# leds.net
KiCad netlist of a schematic drawn in EAGLE
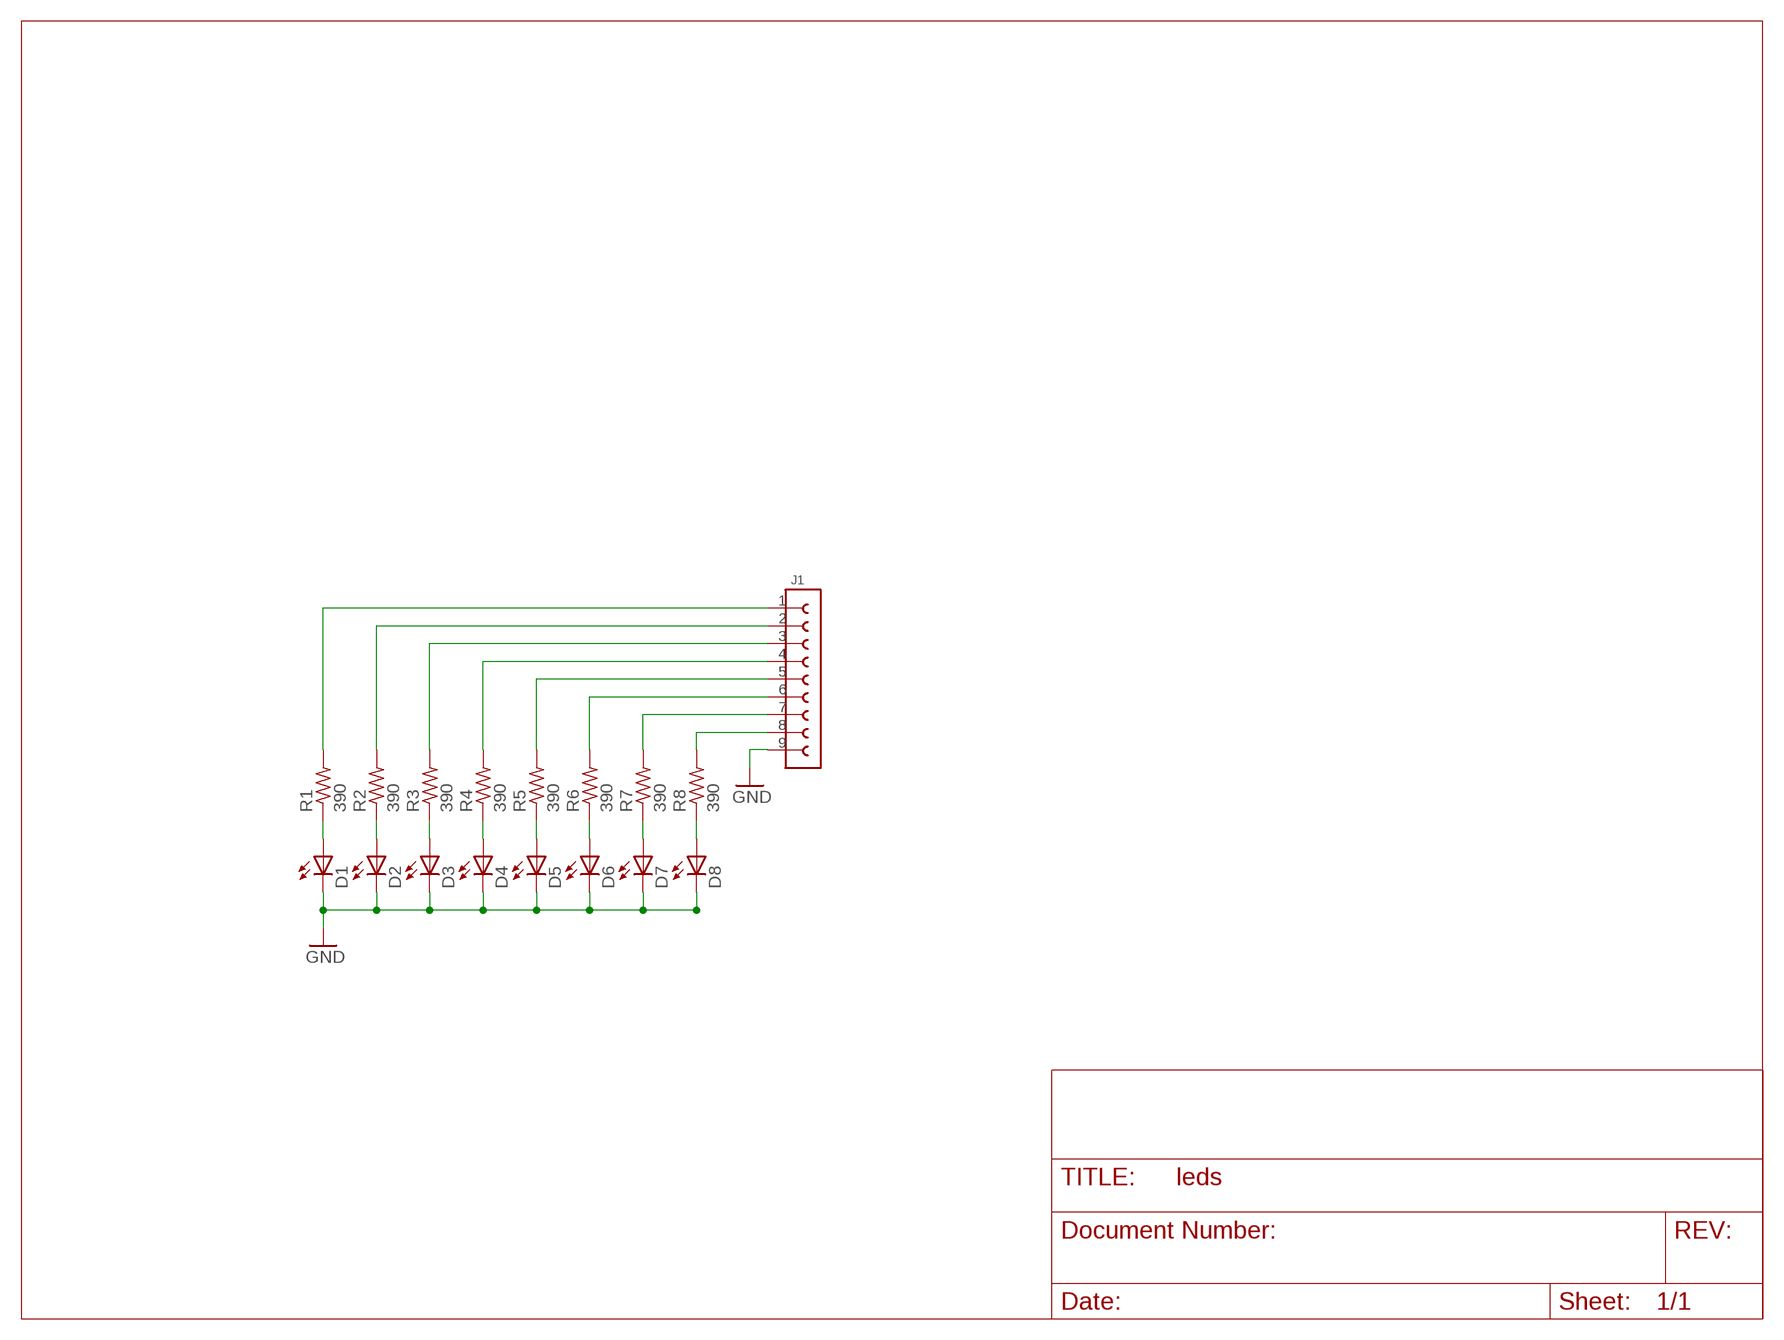
[diagram p0: schematic, sheet 1]

(export (version "E")
  (design (tool "Eeschema 10.0.6"))
  (components
    (comp (ref "D1")
      (value "SM0805AC")
      (footprint "eagle-import:D0805")
      (libsource (lib "eagle-import") (part "SM0805AC"))
    )
    (comp (ref "D2")
      (value "SM0805AC")
      (footprint "eagle-import:D0805")
      (libsource (lib "eagle-import") (part "SM0805AC"))
    )
    (comp (ref "D3")
      (value "SM0805AC")
      (footprint "eagle-import:D0805")
      (libsource (lib "eagle-import") (part "SM0805AC"))
    )
    (comp (ref "D4")
      (value "SM0805AC")
      (footprint "eagle-import:D0805")
      (libsource (lib "eagle-import") (part "SM0805AC"))
    )
    (comp (ref "D5")
      (value "SM0805AC")
      (footprint "eagle-import:D0805")
      (libsource (lib "eagle-import") (part "SM0805AC"))
    )
    (comp (ref "D6")
      (value "SM0805AC")
      (footprint "eagle-import:D0805")
      (libsource (lib "eagle-import") (part "SM0805AC"))
    )
    (comp (ref "D7")
      (value "SM0805AC")
      (footprint "eagle-import:D0805")
      (libsource (lib "eagle-import") (part "SM0805AC"))
    )
    (comp (ref "D8")
      (value "SM0805AC")
      (footprint "eagle-import:D0805")
      (libsource (lib "eagle-import") (part "SM0805AC"))
    )
    (comp (ref "J1")
      (value "61300911121")
      (footprint "eagle-import:PHSP254P2286X254X1154-9S")
      (libsource (lib "eagle-import") (part "6130091?1121"))
    )
    (comp (ref "R1")
      (value "390")
      (footprint "eagle-import:RESC0603")
      (libsource (lib "eagle-import") (part "CRG?0603F390R"))
    )
    (comp (ref "R2")
      (value "390")
      (footprint "eagle-import:RESC0603")
      (libsource (lib "eagle-import") (part "CRG?0603F390R"))
    )
    (comp (ref "R3")
      (value "390")
      (footprint "eagle-import:RESC0603")
      (libsource (lib "eagle-import") (part "CRG?0603F390R"))
    )
    (comp (ref "R4")
      (value "390")
      (footprint "eagle-import:RESC0603")
      (libsource (lib "eagle-import") (part "CRG?0603F390R"))
    )
    (comp (ref "R5")
      (value "390")
      (footprint "eagle-import:RESC0603")
      (libsource (lib "eagle-import") (part "CRG?0603F390R"))
    )
    (comp (ref "R6")
      (value "390")
      (footprint "eagle-import:RESC0603")
      (libsource (lib "eagle-import") (part "CRG?0603F390R"))
    )
    (comp (ref "R7")
      (value "390")
      (footprint "eagle-import:RESC0603")
      (libsource (lib "eagle-import") (part "CRG?0603F390R"))
    )
    (comp (ref "R8")
      (value "390")
      (footprint "eagle-import:RESC0603")
      (libsource (lib "eagle-import") (part "CRG?0603F390R"))
    )
  )
  (nets
    (net (code "1") (name "GND") (class "Default")
      (node (ref "D1") (pin "2") (pinfunction "C_2") (pintype "passive"))
      (node (ref "D2") (pin "2") (pinfunction "C_2") (pintype "passive"))
      (node (ref "D3") (pin "2") (pinfunction "C_2") (pintype "passive"))
      (node (ref "D4") (pin "2") (pinfunction "C_2") (pintype "passive"))
      (node (ref "D5") (pin "2") (pinfunction "C_2") (pintype "passive"))
      (node (ref "D6") (pin "2") (pinfunction "C_2") (pintype "passive"))
      (node (ref "D7") (pin "2") (pinfunction "C_2") (pintype "passive"))
      (node (ref "D8") (pin "2") (pinfunction "C_2") (pintype "passive"))
      (node (ref "J1") (pin "9") (pinfunction "9_9") (pintype "passive"))
    )
    (net (code "2") (name "Net-(D1-A)") (class "Default")
      (node (ref "D1") (pin "1") (pinfunction "A_1") (pintype "passive"))
      (node (ref "R1") (pin "P$1") (pinfunction "1_P$1") (pintype "passive"))
    )
    (net (code "3") (name "Net-(D2-A)") (class "Default")
      (node (ref "D2") (pin "1") (pinfunction "A_1") (pintype "passive"))
      (node (ref "R2") (pin "P$1") (pinfunction "1_P$1") (pintype "passive"))
    )
    (net (code "4") (name "Net-(D3-A)") (class "Default")
      (node (ref "D3") (pin "1") (pinfunction "A_1") (pintype "passive"))
      (node (ref "R3") (pin "P$1") (pinfunction "1_P$1") (pintype "passive"))
    )
    (net (code "5") (name "Net-(D4-A)") (class "Default")
      (node (ref "D4") (pin "1") (pinfunction "A_1") (pintype "passive"))
      (node (ref "R4") (pin "P$1") (pinfunction "1_P$1") (pintype "passive"))
    )
    (net (code "6") (name "Net-(D5-A)") (class "Default")
      (node (ref "D5") (pin "1") (pinfunction "A_1") (pintype "passive"))
      (node (ref "R5") (pin "P$1") (pinfunction "1_P$1") (pintype "passive"))
    )
    (net (code "7") (name "Net-(D6-A)") (class "Default")
      (node (ref "D6") (pin "1") (pinfunction "A_1") (pintype "passive"))
      (node (ref "R6") (pin "P$1") (pinfunction "1_P$1") (pintype "passive"))
    )
    (net (code "8") (name "Net-(D7-A)") (class "Default")
      (node (ref "D7") (pin "1") (pinfunction "A_1") (pintype "passive"))
      (node (ref "R7") (pin "P$1") (pinfunction "1_P$1") (pintype "passive"))
    )
    (net (code "9") (name "Net-(D8-A)") (class "Default")
      (node (ref "D8") (pin "1") (pinfunction "A_1") (pintype "passive"))
      (node (ref "R8") (pin "P$1") (pinfunction "1_P$1") (pintype "passive"))
    )
    (net (code "10") (name "Net-(R1-2)") (class "Default")
      (node (ref "J1") (pin "1") (pinfunction "1_1") (pintype "passive"))
      (node (ref "R1") (pin "P$2") (pinfunction "2_P$2") (pintype "passive"))
    )
    (net (code "11") (name "Net-(R2-2)") (class "Default")
      (node (ref "J1") (pin "2") (pinfunction "2_2") (pintype "passive"))
      (node (ref "R2") (pin "P$2") (pinfunction "2_P$2") (pintype "passive"))
    )
    (net (code "12") (name "Net-(R3-2)") (class "Default")
      (node (ref "J1") (pin "3") (pinfunction "3_3") (pintype "passive"))
      (node (ref "R3") (pin "P$2") (pinfunction "2_P$2") (pintype "passive"))
    )
    (net (code "13") (name "Net-(R4-2)") (class "Default")
      (node (ref "J1") (pin "4") (pinfunction "4_4") (pintype "passive"))
      (node (ref "R4") (pin "P$2") (pinfunction "2_P$2") (pintype "passive"))
    )
    (net (code "14") (name "Net-(R5-2)") (class "Default")
      (node (ref "J1") (pin "5") (pinfunction "5_5") (pintype "passive"))
      (node (ref "R5") (pin "P$2") (pinfunction "2_P$2") (pintype "passive"))
    )
    (net (code "15") (name "Net-(R6-2)") (class "Default")
      (node (ref "J1") (pin "6") (pinfunction "6_6") (pintype "passive"))
      (node (ref "R6") (pin "P$2") (pinfunction "2_P$2") (pintype "passive"))
    )
    (net (code "16") (name "Net-(R7-2)") (class "Default")
      (node (ref "J1") (pin "7") (pinfunction "7_7") (pintype "passive"))
      (node (ref "R7") (pin "P$2") (pinfunction "2_P$2") (pintype "passive"))
    )
    (net (code "17") (name "Net-(R8-2)") (class "Default")
      (node (ref "J1") (pin "8") (pinfunction "8_8") (pintype "passive"))
      (node (ref "R8") (pin "P$2") (pinfunction "2_P$2") (pintype "passive"))
    )
  )
)
